# RasPi-BplusHAT.net
KiCad netlist of a schematic drawn in EAGLE
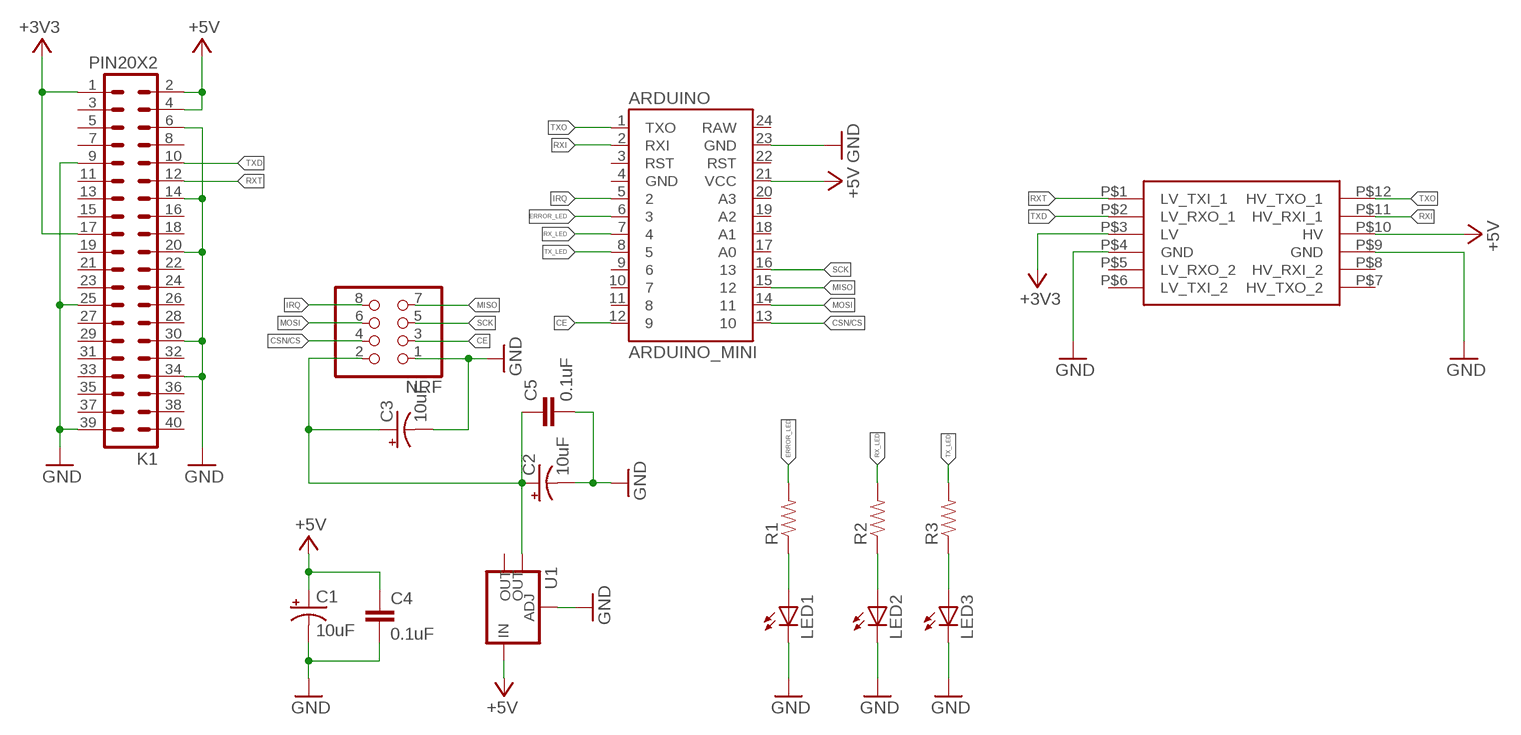
[diagram p0: schematic, sheet 1]

(export (version "E")
  (design (tool "Eeschema 10.0.6"))
  (components
    (comp (ref "ARDUINO")
      (value "ARDUINO_MINI")
      (footprint "eagle-import:ARDUINO_MINI")
      (libsource (lib "eagle-import") (part "ARDUINO_MINI"))
    )
    (comp (ref "C1")
      (value "10uF")
      (footprint "eagle-import:CPOL-RADIAL-10UF-25V")
      (libsource (lib "eagle-import") (part "CAP_POLPTH2"))
    )
    (comp (ref "C2")
      (value "10uF")
      (footprint "eagle-import:CPOL-RADIAL-10UF-25V")
      (libsource (lib "eagle-import") (part "CAP_POLPTH2"))
    )
    (comp (ref "C3")
      (value "10uF")
      (footprint "eagle-import:CPOL-RADIAL-10UF-25V")
      (libsource (lib "eagle-import") (part "CAP_POLPTH2"))
    )
    (comp (ref "C4")
      (value "0.1uF")
      (footprint "eagle-import:CAP-PTH-SMALL")
      (libsource (lib "eagle-import") (part "CAPPTH"))
    )
    (comp (ref "C5")
      (value "0.1uF")
      (footprint "eagle-import:CAP-PTH-SMALL")
      (libsource (lib "eagle-import") (part "CAPPTH"))
    )
    (comp (ref "K1")
      (value "PIN20X2")
      (footprint "eagle-import:PIN_20X2")
      (libsource (lib "eagle-import") (part "PIN20X2"))
    )
    (comp (ref "LED1")
      (value "LED3MM")
      (footprint "eagle-import:LED3MM")
      (libsource (lib "eagle-import") (part "LED3MM"))
    )
    (comp (ref "LED2")
      (value "LED3MM")
      (footprint "eagle-import:LED3MM")
      (libsource (lib "eagle-import") (part "LED3MM"))
    )
    (comp (ref "LED3")
      (value "LED3MM")
      (footprint "eagle-import:LED3MM")
      (libsource (lib "eagle-import") (part "LED3MM"))
    )
    (comp (ref "NRF")
      (value "PINHD-2X4")
      (footprint "eagle-import:2X04")
      (libsource (lib "eagle-import") (part "PINHD-2X4"))
    )
    (comp (ref "R1")
      (value "RESISTORPTH-1/4W")
      (footprint "eagle-import:AXIAL-0.4")
      (libsource (lib "eagle-import") (part "RESISTORPTH-1/4W"))
    )
    (comp (ref "R2")
      (value "RESISTORPTH-1/4W")
      (footprint "eagle-import:AXIAL-0.4")
      (libsource (lib "eagle-import") (part "RESISTORPTH-1/4W"))
    )
    (comp (ref "R3")
      (value "RESISTORPTH-1/4W")
      (footprint "eagle-import:AXIAL-0.4")
      (libsource (lib "eagle-import") (part "RESISTORPTH-1/4W"))
    )
    (comp (ref "U$2")
      (value "LOGIC_LEVEL_CONVERTER")
      (footprint "eagle-import:LOGIC_LEVEL_CONVERTER")
      (libsource (lib "eagle-import") (part "LOGIC_LEVEL_CONVERTER"))
    )
    (comp (ref "U1")
      (value "V_REG_LM1117SOT223")
      (footprint "eagle-import:SOT223")
      (libsource (lib "eagle-import") (part "V_REG_LM1117SOT223"))
    )
  )
  (nets
    (net (code "1") (name "+3V3") (class "Default")
      (node (ref "K1") (pin "1") (pinfunction "1_1") (pintype "passive"))
      (node (ref "K1") (pin "17") (pinfunction "17_17") (pintype "passive"))
      (node (ref "U$2") (pin "P$3") (pinfunction "LV_P$3") (pintype "bidirectional"))
    )
    (net (code "2") (name "+5V") (class "Default")
      (node (ref "ARDUINO") (pin "21") (pinfunction "VCC_21") (pintype "bidirectional"))
      (node (ref "C1") (pin "1") (pinfunction "+_1") (pintype "passive"))
      (node (ref "C4") (pin "1") (pinfunction "1_1") (pintype "passive"))
      (node (ref "K1") (pin "2") (pinfunction "2_2") (pintype "passive"))
      (node (ref "K1") (pin "4") (pinfunction "4_4") (pintype "passive"))
      (node (ref "U$2") (pin "P$10") (pinfunction "HV_P$10") (pintype "bidirectional"))
      (node (ref "U1") (pin "3") (pinfunction "IN_3") (pintype "input"))
    )
    (net (code "3") (name "CE") (class "Default")
      (node (ref "ARDUINO") (pin "12") (pinfunction "9_12") (pintype "bidirectional"))
      (node (ref "NRF") (pin "3") (pinfunction "3_3") (pintype "passive"))
    )
    (net (code "4") (name "CSN{slash}CS") (class "Default")
      (node (ref "ARDUINO") (pin "13") (pinfunction "10_13") (pintype "bidirectional"))
      (node (ref "NRF") (pin "4") (pinfunction "4_4") (pintype "passive"))
    )
    (net (code "5") (name "ERROR_LED") (class "Default")
      (node (ref "ARDUINO") (pin "6") (pinfunction "3_6") (pintype "bidirectional"))
      (node (ref "R1") (pin "P$2") (pinfunction "2_P$2") (pintype "passive"))
    )
    (net (code "6") (name "GND") (class "Default")
      (node (ref "ARDUINO") (pin "23") (pinfunction "GND_23") (pintype "bidirectional"))
      (node (ref "C1") (pin "2") (pinfunction "-_2") (pintype "passive"))
      (node (ref "C2") (pin "2") (pinfunction "-_2") (pintype "passive"))
      (node (ref "C3") (pin "2") (pinfunction "-_2") (pintype "passive"))
      (node (ref "C4") (pin "2") (pinfunction "2_2") (pintype "passive"))
      (node (ref "C5") (pin "2") (pinfunction "2_2") (pintype "passive"))
      (node (ref "K1") (pin "14") (pinfunction "14_14") (pintype "passive"))
      (node (ref "K1") (pin "20") (pinfunction "20_20") (pintype "passive"))
      (node (ref "K1") (pin "25") (pinfunction "25_25") (pintype "passive"))
      (node (ref "K1") (pin "30") (pinfunction "30_30") (pintype "passive"))
      (node (ref "K1") (pin "34") (pinfunction "34_34") (pintype "passive"))
      (node (ref "K1") (pin "39") (pinfunction "39_39") (pintype "passive"))
      (node (ref "K1") (pin "6") (pinfunction "6_6") (pintype "passive"))
      (node (ref "K1") (pin "9") (pinfunction "9_9") (pintype "passive"))
      (node (ref "LED1") (pin "K") (pinfunction "C_K") (pintype "passive"))
      (node (ref "LED2") (pin "K") (pinfunction "C_K") (pintype "passive"))
      (node (ref "LED3") (pin "K") (pinfunction "C_K") (pintype "passive"))
      (node (ref "NRF") (pin "1") (pinfunction "1_1") (pintype "passive"))
      (node (ref "U$2") (pin "P$4") (pinfunction "GND_P$4") (pintype "bidirectional"))
      (node (ref "U$2") (pin "P$9") (pinfunction "GND_P$9") (pintype "bidirectional"))
      (node (ref "U1") (pin "1") (pinfunction "ADJ_1") (pintype "input"))
    )
    (net (code "7") (name "IRQ") (class "Default")
      (node (ref "ARDUINO") (pin "5") (pinfunction "2_5") (pintype "bidirectional"))
      (node (ref "NRF") (pin "8") (pinfunction "8_8") (pintype "passive"))
    )
    (net (code "8") (name "MISO") (class "Default")
      (node (ref "ARDUINO") (pin "15") (pinfunction "12_15") (pintype "bidirectional"))
      (node (ref "NRF") (pin "7") (pinfunction "7_7") (pintype "passive"))
    )
    (net (code "9") (name "MOSI") (class "Default")
      (node (ref "ARDUINO") (pin "14") (pinfunction "11_14") (pintype "bidirectional"))
      (node (ref "NRF") (pin "6") (pinfunction "6_6") (pintype "passive"))
    )
    (net (code "10") (name "Net-(C2-+)") (class "Default")
      (node (ref "C2") (pin "1") (pinfunction "+_1") (pintype "passive"))
      (node (ref "C3") (pin "1") (pinfunction "+_1") (pintype "passive"))
      (node (ref "C5") (pin "1") (pinfunction "1_1") (pintype "passive"))
      (node (ref "NRF") (pin "2") (pinfunction "2_2") (pintype "passive"))
      (node (ref "U1") (pin "4") (pinfunction "OUT_4") (pintype "output"))
    )
    (net (code "11") (name "Net-(R1-1)") (class "Default")
      (node (ref "LED1") (pin "A") (pinfunction "A_A") (pintype "passive"))
      (node (ref "R1") (pin "P$1") (pinfunction "1_P$1") (pintype "passive"))
    )
    (net (code "12") (name "Net-(R2-1)") (class "Default")
      (node (ref "LED2") (pin "A") (pinfunction "A_A") (pintype "passive"))
      (node (ref "R2") (pin "P$1") (pinfunction "1_P$1") (pintype "passive"))
    )
    (net (code "13") (name "Net-(R3-1)") (class "Default")
      (node (ref "LED3") (pin "A") (pinfunction "A_A") (pintype "passive"))
      (node (ref "R3") (pin "P$1") (pinfunction "1_P$1") (pintype "passive"))
    )
    (net (code "14") (name "RXI") (class "Default")
      (node (ref "ARDUINO") (pin "2") (pinfunction "RXI_2") (pintype "bidirectional"))
      (node (ref "U$2") (pin "P$11") (pinfunction "HV_RXI_1_P$11") (pintype "bidirectional"))
    )
    (net (code "15") (name "RXT") (class "Default")
      (node (ref "K1") (pin "12") (pinfunction "12_12") (pintype "passive"))
      (node (ref "U$2") (pin "P$1") (pinfunction "LV_TXI_1_P$1") (pintype "bidirectional"))
    )
    (net (code "16") (name "RX_LED") (class "Default")
      (node (ref "ARDUINO") (pin "7") (pinfunction "4_7") (pintype "bidirectional"))
      (node (ref "R2") (pin "P$2") (pinfunction "2_P$2") (pintype "passive"))
    )
    (net (code "17") (name "SCK") (class "Default")
      (node (ref "ARDUINO") (pin "16") (pinfunction "13_16") (pintype "bidirectional"))
      (node (ref "NRF") (pin "5") (pinfunction "5_5") (pintype "passive"))
    )
    (net (code "18") (name "TXD") (class "Default")
      (node (ref "K1") (pin "10") (pinfunction "10_10") (pintype "passive"))
      (node (ref "U$2") (pin "P$2") (pinfunction "LV_RXO_1_P$2") (pintype "bidirectional"))
    )
    (net (code "19") (name "TXO") (class "Default")
      (node (ref "ARDUINO") (pin "1") (pinfunction "TXO_1") (pintype "bidirectional"))
      (node (ref "U$2") (pin "P$12") (pinfunction "HV_TXO_1_P$12") (pintype "bidirectional"))
    )
    (net (code "20") (name "TX_LED") (class "Default")
      (node (ref "ARDUINO") (pin "8") (pinfunction "5_8") (pintype "bidirectional"))
      (node (ref "R3") (pin "P$2") (pinfunction "2_P$2") (pintype "passive"))
    )
    (net (code "21") (name "unconnected-(ARDUINO-6-Pad9)") (class "Default")
      (node (ref "ARDUINO") (pin "9") (pinfunction "6_9") (pintype "bidirectional"))
    )
    (net (code "22") (name "unconnected-(ARDUINO-7-Pad10)") (class "Default")
      (node (ref "ARDUINO") (pin "10") (pinfunction "7_10") (pintype "bidirectional"))
    )
    (net (code "23") (name "unconnected-(ARDUINO-8-Pad11)") (class "Default")
      (node (ref "ARDUINO") (pin "11") (pinfunction "8_11") (pintype "bidirectional"))
    )
    (net (code "24") (name "unconnected-(ARDUINO-A0-Pad17)") (class "Default")
      (node (ref "ARDUINO") (pin "17") (pinfunction "A0_17") (pintype "bidirectional"))
    )
    (net (code "25") (name "unconnected-(ARDUINO-A1-Pad18)") (class "Default")
      (node (ref "ARDUINO") (pin "18") (pinfunction "A1_18") (pintype "bidirectional"))
    )
    (net (code "26") (name "unconnected-(ARDUINO-A2-Pad19)") (class "Default")
      (node (ref "ARDUINO") (pin "19") (pinfunction "A2_19") (pintype "bidirectional"))
    )
    (net (code "27") (name "unconnected-(ARDUINO-A3-Pad20)") (class "Default")
      (node (ref "ARDUINO") (pin "20") (pinfunction "A3_20") (pintype "bidirectional"))
    )
    (net (code "28") (name "unconnected-(ARDUINO-GND-Pad4)") (class "Default")
      (node (ref "ARDUINO") (pin "4") (pinfunction "GND_4") (pintype "bidirectional"))
    )
    (net (code "29") (name "unconnected-(ARDUINO-RAW-Pad24)") (class "Default")
      (node (ref "ARDUINO") (pin "24") (pinfunction "RAW_24") (pintype "bidirectional"))
    )
    (net (code "30") (name "unconnected-(ARDUINO-RST-Pad3)") (class "Default")
      (node (ref "ARDUINO") (pin "3") (pinfunction "RST_3") (pintype "bidirectional"))
    )
    (net (code "31") (name "unconnected-(ARDUINO-RST-Pad22)") (class "Default")
      (node (ref "ARDUINO") (pin "22") (pinfunction "RST_22") (pintype "bidirectional"))
    )
    (net (code "32") (name "unconnected-(K1-Pad3)") (class "Default")
      (node (ref "K1") (pin "3") (pinfunction "3_3") (pintype "passive"))
    )
    (net (code "33") (name "unconnected-(K1-Pad5)") (class "Default")
      (node (ref "K1") (pin "5") (pinfunction "5_5") (pintype "passive"))
    )
    (net (code "34") (name "unconnected-(K1-Pad7)") (class "Default")
      (node (ref "K1") (pin "7") (pinfunction "7_7") (pintype "passive"))
    )
    (net (code "35") (name "unconnected-(K1-Pad8)") (class "Default")
      (node (ref "K1") (pin "8") (pinfunction "8_8") (pintype "passive"))
    )
    (net (code "36") (name "unconnected-(K1-Pad11)") (class "Default")
      (node (ref "K1") (pin "11") (pinfunction "11_11") (pintype "passive"))
    )
    (net (code "37") (name "unconnected-(K1-Pad13)") (class "Default")
      (node (ref "K1") (pin "13") (pinfunction "13_13") (pintype "passive"))
    )
    (net (code "38") (name "unconnected-(K1-Pad15)") (class "Default")
      (node (ref "K1") (pin "15") (pinfunction "15_15") (pintype "passive"))
    )
    (net (code "39") (name "unconnected-(K1-Pad16)") (class "Default")
      (node (ref "K1") (pin "16") (pinfunction "16_16") (pintype "passive"))
    )
    (net (code "40") (name "unconnected-(K1-Pad18)") (class "Default")
      (node (ref "K1") (pin "18") (pinfunction "18_18") (pintype "passive"))
    )
    (net (code "41") (name "unconnected-(K1-Pad19)") (class "Default")
      (node (ref "K1") (pin "19") (pinfunction "19_19") (pintype "passive"))
    )
    (net (code "42") (name "unconnected-(K1-Pad21)") (class "Default")
      (node (ref "K1") (pin "21") (pinfunction "21_21") (pintype "passive"))
    )
    (net (code "43") (name "unconnected-(K1-Pad22)") (class "Default")
      (node (ref "K1") (pin "22") (pinfunction "22_22") (pintype "passive"))
    )
    (net (code "44") (name "unconnected-(K1-Pad23)") (class "Default")
      (node (ref "K1") (pin "23") (pinfunction "23_23") (pintype "passive"))
    )
    (net (code "45") (name "unconnected-(K1-Pad24)") (class "Default")
      (node (ref "K1") (pin "24") (pinfunction "24_24") (pintype "passive"))
    )
    (net (code "46") (name "unconnected-(K1-Pad26)") (class "Default")
      (node (ref "K1") (pin "26") (pinfunction "26_26") (pintype "passive"))
    )
    (net (code "47") (name "unconnected-(K1-Pad27)") (class "Default")
      (node (ref "K1") (pin "27") (pinfunction "27_27") (pintype "passive"))
    )
    (net (code "48") (name "unconnected-(K1-Pad28)") (class "Default")
      (node (ref "K1") (pin "28") (pinfunction "28_28") (pintype "passive"))
    )
    (net (code "49") (name "unconnected-(K1-Pad29)") (class "Default")
      (node (ref "K1") (pin "29") (pinfunction "29_29") (pintype "passive"))
    )
    (net (code "50") (name "unconnected-(K1-Pad31)") (class "Default")
      (node (ref "K1") (pin "31") (pinfunction "31_31") (pintype "passive"))
    )
    (net (code "51") (name "unconnected-(K1-Pad32)") (class "Default")
      (node (ref "K1") (pin "32") (pinfunction "32_32") (pintype "passive"))
    )
    (net (code "52") (name "unconnected-(K1-Pad33)") (class "Default")
      (node (ref "K1") (pin "33") (pinfunction "33_33") (pintype "passive"))
    )
    (net (code "53") (name "unconnected-(K1-Pad35)") (class "Default")
      (node (ref "K1") (pin "35") (pinfunction "35_35") (pintype "passive"))
    )
    (net (code "54") (name "unconnected-(K1-Pad36)") (class "Default")
      (node (ref "K1") (pin "36") (pinfunction "36_36") (pintype "passive"))
    )
    (net (code "55") (name "unconnected-(K1-Pad37)") (class "Default")
      (node (ref "K1") (pin "37") (pinfunction "37_37") (pintype "passive"))
    )
    (net (code "56") (name "unconnected-(K1-Pad38)") (class "Default")
      (node (ref "K1") (pin "38") (pinfunction "38_38") (pintype "passive"))
    )
    (net (code "57") (name "unconnected-(K1-Pad40)") (class "Default")
      (node (ref "K1") (pin "40") (pinfunction "40_40") (pintype "passive"))
    )
    (net (code "58") (name "unconnected-(U$2-HV_RXI_2-PadP$8)") (class "Default")
      (node (ref "U$2") (pin "P$8") (pinfunction "HV_RXI_2_P$8") (pintype "bidirectional"))
    )
    (net (code "59") (name "unconnected-(U$2-HV_TXO_2-PadP$7)") (class "Default")
      (node (ref "U$2") (pin "P$7") (pinfunction "HV_TXO_2_P$7") (pintype "bidirectional"))
    )
    (net (code "60") (name "unconnected-(U$2-LV_RXO_2-PadP$5)") (class "Default")
      (node (ref "U$2") (pin "P$5") (pinfunction "LV_RXO_2_P$5") (pintype "bidirectional"))
    )
    (net (code "61") (name "unconnected-(U$2-LV_TXI_2-PadP$6)") (class "Default")
      (node (ref "U$2") (pin "P$6") (pinfunction "LV_TXI_2_P$6") (pintype "bidirectional"))
    )
    (net (code "62") (name "unconnected-(U1-OUT-Pad2)") (class "Default")
      (node (ref "U1") (pin "2") (pinfunction "OUT_2") (pintype "output"))
    )
  )
)
